# nano_carrier_th.net
KiCad netlist of a schematic drawn in EAGLE
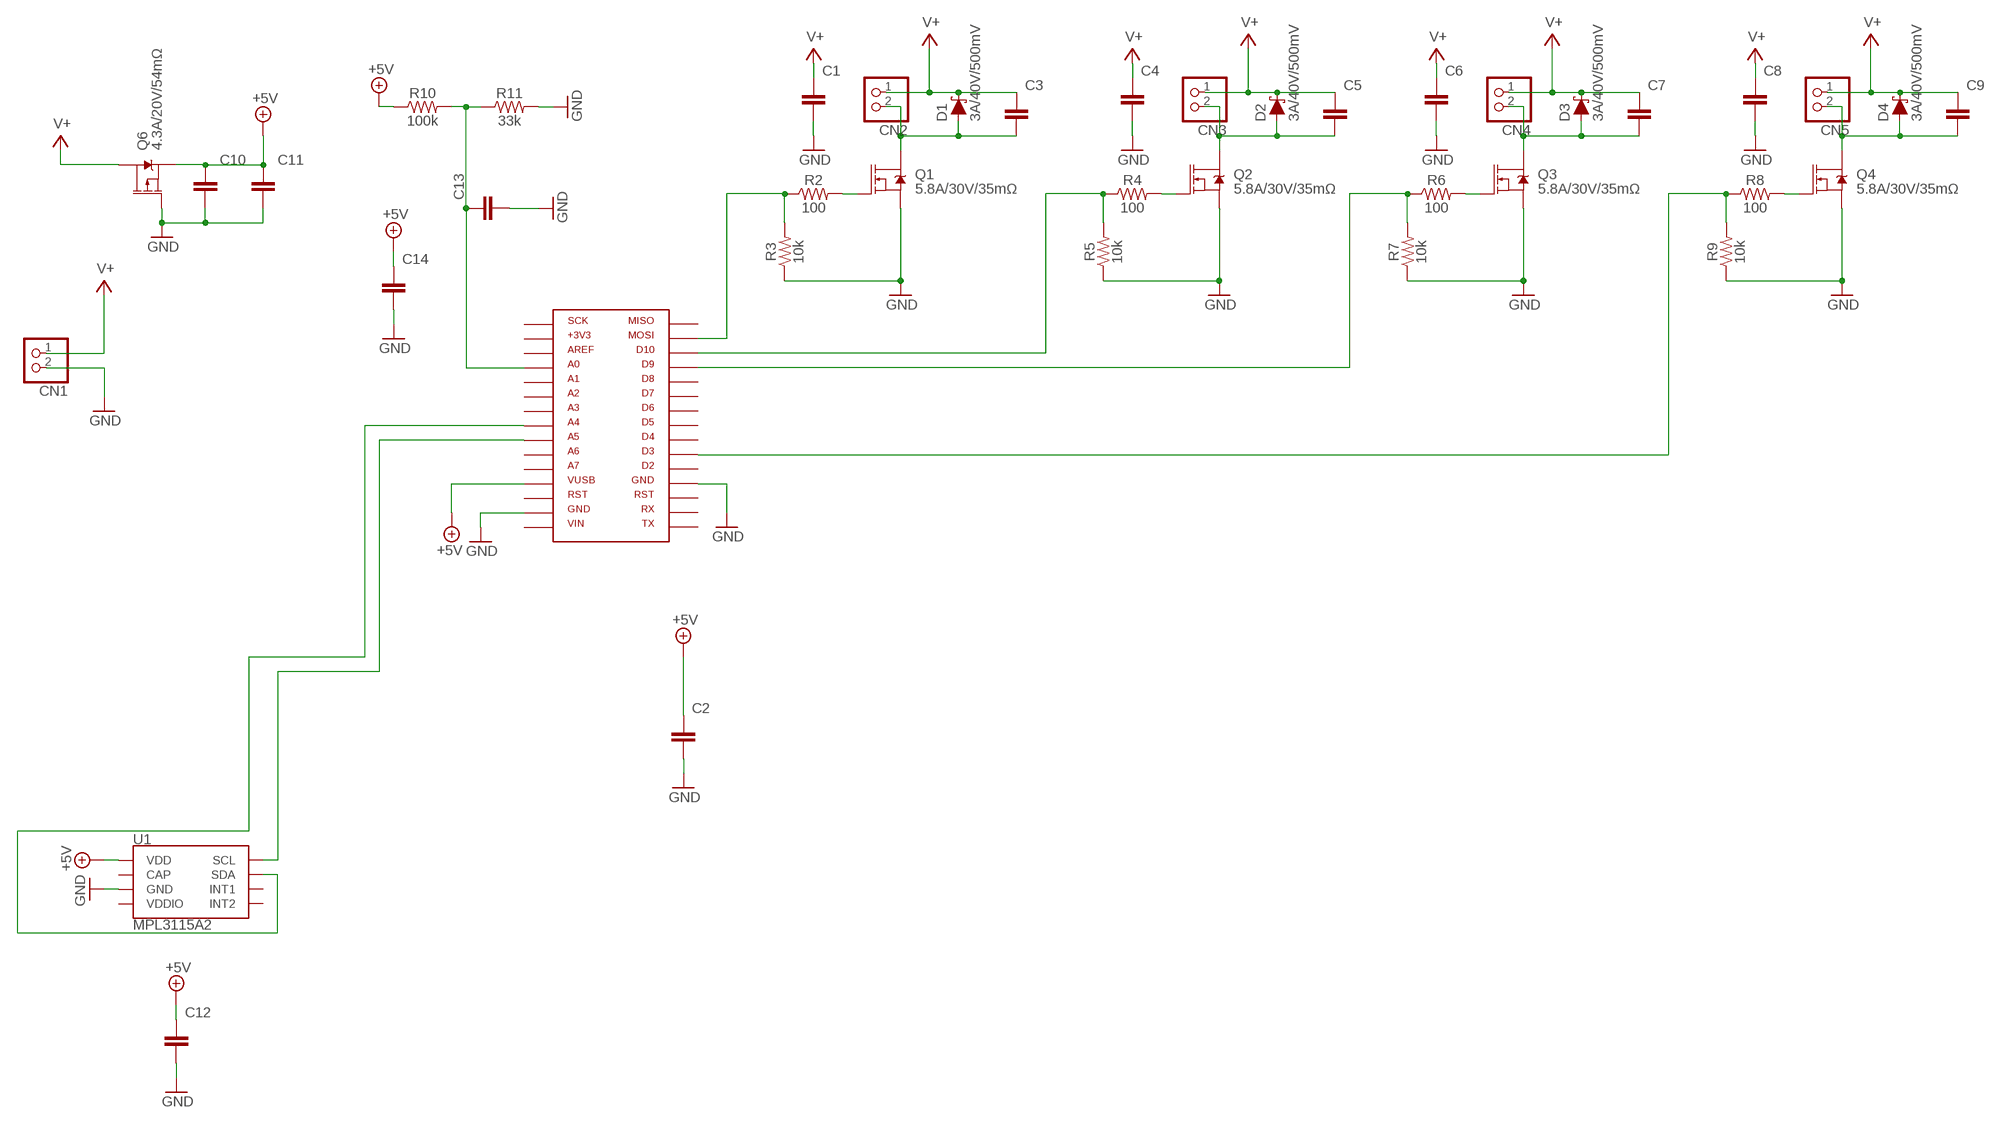
[diagram p0: schematic, sheet 1]

(export (version "E")
  (design (tool "Eeschema 10.0.6"))
  (components
    (comp (ref "C1")
      (value "22uF")
      (footprint "eagle-import:CAPM3216X180")
      (libsource (lib "eagle-import") (part "CTANTALUM-1206(3216-METRIC)_"))
    )
    (comp (ref "C2")
      (value "10uF")
      (footprint "eagle-import:CAPM3216X180")
      (libsource (lib "eagle-import") (part "CTANTALUM-1206(3216-METRIC)_"))
    )
    (comp (ref "C3")
      (value "10nF")
      (footprint "eagle-import:CAPM3216X180")
      (libsource (lib "eagle-import") (part "CTANTALUM-1206(3216-METRIC)_"))
    )
    (comp (ref "C4")
      (value "22uF")
      (footprint "eagle-import:CAPM3216X180")
      (libsource (lib "eagle-import") (part "CTANTALUM-1206(3216-METRIC)_"))
    )
    (comp (ref "C5")
      (value "10nF")
      (footprint "eagle-import:CAPM3216X180")
      (libsource (lib "eagle-import") (part "CTANTALUM-1206(3216-METRIC)_"))
    )
    (comp (ref "C6")
      (value "22uF")
      (footprint "eagle-import:CAPM3216X180")
      (libsource (lib "eagle-import") (part "CTANTALUM-1206(3216-METRIC)_"))
    )
    (comp (ref "C7")
      (value "10nF")
      (footprint "eagle-import:CAPM3216X180")
      (libsource (lib "eagle-import") (part "CTANTALUM-1206(3216-METRIC)_"))
    )
    (comp (ref "C8")
      (value "22uF")
      (footprint "eagle-import:CAPM3216X180")
      (libsource (lib "eagle-import") (part "CTANTALUM-1206(3216-METRIC)_"))
    )
    (comp (ref "C9")
      (value "10nF")
      (footprint "eagle-import:CAPM3216X180")
      (libsource (lib "eagle-import") (part "CTANTALUM-1206(3216-METRIC)_"))
    )
    (comp (ref "C10")
      (value "C_TANTALUM-1206(3216-METRIC)")
      (footprint "eagle-import:CAPM3216X180")
      (libsource (lib "eagle-import") (part "CTANTALUM-1206(3216-METRIC)_"))
    )
    (comp (ref "C11")
      (value "C_TANTALUM-1206(3216-METRIC)")
      (footprint "eagle-import:CAPM3216X180")
      (libsource (lib "eagle-import") (part "CTANTALUM-1206(3216-METRIC)_"))
    )
    (comp (ref "C12")
      (value "22uF")
      (footprint "eagle-import:CAPM3216X180")
      (libsource (lib "eagle-import") (part "CTANTALUM-1206(3216-METRIC)_"))
    )
    (comp (ref "C13")
      (value "22uF")
      (footprint "eagle-import:CAPM3216X180")
      (libsource (lib "eagle-import") (part "CTANTALUM-1206(3216-METRIC)_"))
    )
    (comp (ref "C14")
      (value "22uF")
      (footprint "eagle-import:CAPM3216X180")
      (libsource (lib "eagle-import") (part "CTANTALUM-1206(3216-METRIC)_"))
    )
    (comp (ref "CN1")
      (value "JST_2PIN-THM")
      (footprint "eagle-import:JST-PH-2-THM")
      (libsource (lib "eagle-import") (part "JST_2PIN-THM"))
    )
    (comp (ref "CN2")
      (value "JST_2PIN-THM")
      (footprint "eagle-import:JST-PH-2-THM")
      (libsource (lib "eagle-import") (part "JST_2PIN-THM"))
    )
    (comp (ref "CN3")
      (value "JST_2PIN-THM")
      (footprint "eagle-import:JST-PH-2-THM")
      (libsource (lib "eagle-import") (part "JST_2PIN-THM"))
    )
    (comp (ref "CN4")
      (value "JST_2PIN-THM")
      (footprint "eagle-import:JST-PH-2-THM")
      (libsource (lib "eagle-import") (part "JST_2PIN-THM"))
    )
    (comp (ref "CN5")
      (value "JST_2PIN-THM")
      (footprint "eagle-import:JST-PH-2-THM")
      (libsource (lib "eagle-import") (part "JST_2PIN-THM"))
    )
    (comp (ref "D1")
      (value "3A/40V/500mV")
      (footprint "eagle-import:SMA-DIODE")
      (libsource (lib "eagle-import") (part "DIODE-SCHOTTKY-B340A"))
    )
    (comp (ref "D2")
      (value "3A/40V/500mV")
      (footprint "eagle-import:SMA-DIODE")
      (libsource (lib "eagle-import") (part "DIODE-SCHOTTKY-B340A"))
    )
    (comp (ref "D3")
      (value "3A/40V/500mV")
      (footprint "eagle-import:SMA-DIODE")
      (libsource (lib "eagle-import") (part "DIODE-SCHOTTKY-B340A"))
    )
    (comp (ref "D4")
      (value "3A/40V/500mV")
      (footprint "eagle-import:SMA-DIODE")
      (libsource (lib "eagle-import") (part "DIODE-SCHOTTKY-B340A"))
    )
    (comp (ref "Q1")
      (value "5.8A/30V/35mΩ")
      (footprint "eagle-import:SOT23-3")
      (libsource (lib "eagle-import") (part "MOSFET-NCH-AO3404A"))
    )
    (comp (ref "Q2")
      (value "5.8A/30V/35mΩ")
      (footprint "eagle-import:SOT23-3")
      (libsource (lib "eagle-import") (part "MOSFET-NCH-AO3404A"))
    )
    (comp (ref "Q3")
      (value "5.8A/30V/35mΩ")
      (footprint "eagle-import:SOT23-3")
      (libsource (lib "eagle-import") (part "MOSFET-NCH-AO3404A"))
    )
    (comp (ref "Q4")
      (value "5.8A/30V/35mΩ")
      (footprint "eagle-import:SOT23-3")
      (libsource (lib "eagle-import") (part "MOSFET-NCH-AO3404A"))
    )
    (comp (ref "Q6")
      (value "4.3A/20V/54mΩ")
      (footprint "eagle-import:SOT23-3")
      (libsource (lib "eagle-import") (part "MOSFET_PCH-IRLML2244"))
    )
    (comp (ref "R2")
      (value "100")
      (footprint "eagle-import:0603")
      (libsource (lib "eagle-import") (part "100OHM-0603-1/4W-5%"))
    )
    (comp (ref "R3")
      (value "10k")
      (footprint "eagle-import:0603")
      (libsource (lib "eagle-import") (part "10KOHM-0603-1/10W-1%"))
    )
    (comp (ref "R4")
      (value "100")
      (footprint "eagle-import:0603")
      (libsource (lib "eagle-import") (part "100OHM-0603-1/4W-5%"))
    )
    (comp (ref "R5")
      (value "10k")
      (footprint "eagle-import:0603")
      (libsource (lib "eagle-import") (part "10KOHM-0603-1/10W-1%"))
    )
    (comp (ref "R6")
      (value "100")
      (footprint "eagle-import:0603")
      (libsource (lib "eagle-import") (part "100OHM-0603-1/4W-5%"))
    )
    (comp (ref "R7")
      (value "10k")
      (footprint "eagle-import:0603")
      (libsource (lib "eagle-import") (part "10KOHM-0603-1/10W-1%"))
    )
    (comp (ref "R8")
      (value "100")
      (footprint "eagle-import:0603")
      (libsource (lib "eagle-import") (part "100OHM-0603-1/4W-5%"))
    )
    (comp (ref "R9")
      (value "10k")
      (footprint "eagle-import:0603")
      (libsource (lib "eagle-import") (part "10KOHM-0603-1/10W-1%"))
    )
    (comp (ref "R10")
      (value "100k")
      (footprint "eagle-import:0603")
      (libsource (lib "eagle-import") (part "100KOHM-0603-1/10W-1%"))
    )
    (comp (ref "R11")
      (value "33k")
      (footprint "eagle-import:0603")
      (libsource (lib "eagle-import") (part "33KOHM-0603-1/10W-1%"))
    )
    (comp (ref "U$1")
      (value "NANO-TH")
      (footprint "eagle-import:NANO-TH")
      (libsource (lib "eagle-import") (part "NANO-TH"))
    )
    (comp (ref "U1")
      (value "MPL3115A2")
      (footprint "eagle-import:LGA-8-5X3")
      (libsource (lib "eagle-import") (part "MPL3115A2"))
    )
  )
  (nets
    (net (code "1") (name "+5V") (class "Default")
      (node (ref "C10") (pin "1") (pinfunction "1_1") (pintype "passive"))
      (node (ref "C11") (pin "1") (pinfunction "1_1") (pintype "passive"))
      (node (ref "C12") (pin "1") (pinfunction "1_1") (pintype "passive"))
      (node (ref "C14") (pin "1") (pinfunction "1_1") (pintype "passive"))
      (node (ref "C2") (pin "1") (pinfunction "1_1") (pintype "passive"))
      (node (ref "Q6") (pin "2") (pinfunction "S_2") (pintype "bidirectional"))
      (node (ref "R10") (pin "1") (pinfunction "1_1") (pintype "passive"))
      (node (ref "U$1") (pin "P$12") (pinfunction "P$12_P$12") (pintype "bidirectional"))
      (node (ref "U1") (pin "1") (pinfunction "VDD_1") (pintype "power_in"))
    )
    (net (code "2") (name "/CAP") (class "Default")
      (node (ref "U1") (pin "2") (pinfunction "CAP_2") (pintype "power_in"))
    )
    (net (code "3") (name "/VDDIO") (class "Default")
      (node (ref "U1") (pin "4") (pinfunction "VDDIO_4") (pintype "power_in"))
    )
    (net (code "4") (name "GND") (class "Default")
      (node (ref "C1") (pin "2") (pinfunction "2_2") (pintype "passive"))
      (node (ref "C10") (pin "2") (pinfunction "2_2") (pintype "passive"))
      (node (ref "C11") (pin "2") (pinfunction "2_2") (pintype "passive"))
      (node (ref "C12") (pin "2") (pinfunction "2_2") (pintype "passive"))
      (node (ref "C13") (pin "2") (pinfunction "2_2") (pintype "passive"))
      (node (ref "C14") (pin "2") (pinfunction "2_2") (pintype "passive"))
      (node (ref "C2") (pin "2") (pinfunction "2_2") (pintype "passive"))
      (node (ref "C4") (pin "2") (pinfunction "2_2") (pintype "passive"))
      (node (ref "C6") (pin "2") (pinfunction "2_2") (pintype "passive"))
      (node (ref "C8") (pin "2") (pinfunction "2_2") (pintype "passive"))
      (node (ref "CN1") (pin "2") (pinfunction "1_2") (pintype "passive"))
      (node (ref "Q1") (pin "2") (pinfunction "S_2") (pintype "bidirectional"))
      (node (ref "Q2") (pin "2") (pinfunction "S_2") (pintype "bidirectional"))
      (node (ref "Q3") (pin "2") (pinfunction "S_2") (pintype "bidirectional"))
      (node (ref "Q4") (pin "2") (pinfunction "S_2") (pintype "bidirectional"))
      (node (ref "Q6") (pin "1") (pinfunction "G_1") (pintype "bidirectional"))
      (node (ref "R11") (pin "2") (pinfunction "2_2") (pintype "passive"))
      (node (ref "R3") (pin "1") (pinfunction "1_1") (pintype "passive"))
      (node (ref "R5") (pin "1") (pinfunction "1_1") (pintype "passive"))
      (node (ref "R7") (pin "1") (pinfunction "1_1") (pintype "passive"))
      (node (ref "R9") (pin "1") (pinfunction "1_1") (pintype "passive"))
      (node (ref "U$1") (pin "P$14") (pinfunction "P$14_P$14") (pintype "bidirectional"))
      (node (ref "U$1") (pin "P$19") (pinfunction "P$19_P$19") (pintype "bidirectional"))
      (node (ref "U1") (pin "3") (pinfunction "GND_3") (pintype "power_in"))
    )
    (net (code "5") (name "Net-(C13-Pad1)") (class "Default")
      (node (ref "C13") (pin "1") (pinfunction "1_1") (pintype "passive"))
      (node (ref "R10") (pin "2") (pinfunction "2_2") (pintype "passive"))
      (node (ref "R11") (pin "1") (pinfunction "1_1") (pintype "passive"))
      (node (ref "U$1") (pin "P$4") (pinfunction "P$4_P$4") (pintype "bidirectional"))
    )
    (net (code "6") (name "Net-(CN2-1)") (class "Default")
      (node (ref "C3") (pin "2") (pinfunction "2_2") (pintype "passive"))
      (node (ref "CN2") (pin "2") (pinfunction "1_2") (pintype "passive"))
      (node (ref "D1") (pin "A") (pinfunction "A_A") (pintype "passive"))
      (node (ref "Q1") (pin "3") (pinfunction "D_3") (pintype "bidirectional"))
    )
    (net (code "7") (name "Net-(CN3-1)") (class "Default")
      (node (ref "C5") (pin "2") (pinfunction "2_2") (pintype "passive"))
      (node (ref "CN3") (pin "2") (pinfunction "1_2") (pintype "passive"))
      (node (ref "D2") (pin "A") (pinfunction "A_A") (pintype "passive"))
      (node (ref "Q2") (pin "3") (pinfunction "D_3") (pintype "bidirectional"))
    )
    (net (code "8") (name "Net-(CN4-1)") (class "Default")
      (node (ref "C7") (pin "2") (pinfunction "2_2") (pintype "passive"))
      (node (ref "CN4") (pin "2") (pinfunction "1_2") (pintype "passive"))
      (node (ref "D3") (pin "A") (pinfunction "A_A") (pintype "passive"))
      (node (ref "Q3") (pin "3") (pinfunction "D_3") (pintype "bidirectional"))
    )
    (net (code "9") (name "Net-(CN5-1)") (class "Default")
      (node (ref "C9") (pin "2") (pinfunction "2_2") (pintype "passive"))
      (node (ref "CN5") (pin "2") (pinfunction "1_2") (pintype "passive"))
      (node (ref "D4") (pin "A") (pinfunction "A_A") (pintype "passive"))
      (node (ref "Q4") (pin "3") (pinfunction "D_3") (pintype "bidirectional"))
    )
    (net (code "10") (name "Net-(Q1-G)") (class "Default")
      (node (ref "Q1") (pin "1") (pinfunction "G_1") (pintype "bidirectional"))
      (node (ref "R2") (pin "2") (pinfunction "2_2") (pintype "passive"))
    )
    (net (code "11") (name "Net-(Q2-G)") (class "Default")
      (node (ref "Q2") (pin "1") (pinfunction "G_1") (pintype "bidirectional"))
      (node (ref "R4") (pin "2") (pinfunction "2_2") (pintype "passive"))
    )
    (net (code "12") (name "Net-(Q3-G)") (class "Default")
      (node (ref "Q3") (pin "1") (pinfunction "G_1") (pintype "bidirectional"))
      (node (ref "R6") (pin "2") (pinfunction "2_2") (pintype "passive"))
    )
    (net (code "13") (name "Net-(Q4-G)") (class "Default")
      (node (ref "Q4") (pin "1") (pinfunction "G_1") (pintype "bidirectional"))
      (node (ref "R8") (pin "2") (pinfunction "2_2") (pintype "passive"))
    )
    (net (code "14") (name "Net-(R2-Pad1)") (class "Default")
      (node (ref "R2") (pin "1") (pinfunction "1_1") (pintype "passive"))
      (node (ref "R3") (pin "2") (pinfunction "2_2") (pintype "passive"))
      (node (ref "U$1") (pin "P$29") (pinfunction "P$29_P$29") (pintype "bidirectional"))
    )
    (net (code "15") (name "Net-(R4-Pad1)") (class "Default")
      (node (ref "R4") (pin "1") (pinfunction "1_1") (pintype "passive"))
      (node (ref "R5") (pin "2") (pinfunction "2_2") (pintype "passive"))
      (node (ref "U$1") (pin "P$28") (pinfunction "P$28_P$28") (pintype "bidirectional"))
    )
    (net (code "16") (name "Net-(R6-Pad1)") (class "Default")
      (node (ref "R6") (pin "1") (pinfunction "1_1") (pintype "passive"))
      (node (ref "R7") (pin "2") (pinfunction "2_2") (pintype "passive"))
      (node (ref "U$1") (pin "P$27") (pinfunction "P$27_P$27") (pintype "bidirectional"))
    )
    (net (code "17") (name "Net-(R8-Pad1)") (class "Default")
      (node (ref "R8") (pin "1") (pinfunction "1_1") (pintype "passive"))
      (node (ref "R9") (pin "2") (pinfunction "2_2") (pintype "passive"))
      (node (ref "U$1") (pin "P$21") (pinfunction "P$21_P$21") (pintype "bidirectional"))
    )
    (net (code "18") (name "Net-(U1-SCL)") (class "Default")
      (node (ref "U$1") (pin "P$9") (pinfunction "P$9_P$9") (pintype "bidirectional"))
      (node (ref "U1") (pin "8") (pinfunction "SCL_8") (pintype "bidirectional"))
    )
    (net (code "19") (name "Net-(U1-SDA)") (class "Default")
      (node (ref "U$1") (pin "P$8") (pinfunction "P$8_P$8") (pintype "bidirectional"))
      (node (ref "U1") (pin "7") (pinfunction "SDA_7") (pintype "bidirectional"))
    )
    (net (code "20") (name "V+") (class "Default")
      (node (ref "C1") (pin "1") (pinfunction "1_1") (pintype "passive"))
      (node (ref "C3") (pin "1") (pinfunction "1_1") (pintype "passive"))
      (node (ref "C4") (pin "1") (pinfunction "1_1") (pintype "passive"))
      (node (ref "C5") (pin "1") (pinfunction "1_1") (pintype "passive"))
      (node (ref "C6") (pin "1") (pinfunction "1_1") (pintype "passive"))
      (node (ref "C7") (pin "1") (pinfunction "1_1") (pintype "passive"))
      (node (ref "C8") (pin "1") (pinfunction "1_1") (pintype "passive"))
      (node (ref "C9") (pin "1") (pinfunction "1_1") (pintype "passive"))
      (node (ref "CN1") (pin "1") (pinfunction "2_1") (pintype "passive"))
      (node (ref "CN2") (pin "1") (pinfunction "2_1") (pintype "passive"))
      (node (ref "CN3") (pin "1") (pinfunction "2_1") (pintype "passive"))
      (node (ref "CN4") (pin "1") (pinfunction "2_1") (pintype "passive"))
      (node (ref "CN5") (pin "1") (pinfunction "2_1") (pintype "passive"))
      (node (ref "D1") (pin "C") (pinfunction "C_C") (pintype "passive"))
      (node (ref "D2") (pin "C") (pinfunction "C_C") (pintype "passive"))
      (node (ref "D3") (pin "C") (pinfunction "C_C") (pintype "passive"))
      (node (ref "D4") (pin "C") (pinfunction "C_C") (pintype "passive"))
      (node (ref "Q6") (pin "3") (pinfunction "D_3") (pintype "bidirectional"))
    )
    (net (code "21") (name "unconnected-(U$1-PadP$1)") (class "Default")
      (node (ref "U$1") (pin "P$1") (pinfunction "P$1_P$1") (pintype "bidirectional"))
    )
    (net (code "22") (name "unconnected-(U$1-PadP$2)") (class "Default")
      (node (ref "U$1") (pin "P$2") (pinfunction "P$2_P$2") (pintype "bidirectional"))
    )
    (net (code "23") (name "unconnected-(U$1-PadP$3)") (class "Default")
      (node (ref "U$1") (pin "P$3") (pinfunction "P$3_P$3") (pintype "bidirectional"))
    )
    (net (code "24") (name "unconnected-(U$1-PadP$5)") (class "Default")
      (node (ref "U$1") (pin "P$5") (pinfunction "P$5_P$5") (pintype "bidirectional"))
    )
    (net (code "25") (name "unconnected-(U$1-PadP$6)") (class "Default")
      (node (ref "U$1") (pin "P$6") (pinfunction "P$6_P$6") (pintype "bidirectional"))
    )
    (net (code "26") (name "unconnected-(U$1-PadP$7)") (class "Default")
      (node (ref "U$1") (pin "P$7") (pinfunction "P$7_P$7") (pintype "bidirectional"))
    )
    (net (code "27") (name "unconnected-(U$1-PadP$10)") (class "Default")
      (node (ref "U$1") (pin "P$10") (pinfunction "P$10_P$10") (pintype "bidirectional"))
    )
    (net (code "28") (name "unconnected-(U$1-PadP$11)") (class "Default")
      (node (ref "U$1") (pin "P$11") (pinfunction "P$11_P$11") (pintype "bidirectional"))
    )
    (net (code "29") (name "unconnected-(U$1-PadP$13)") (class "Default")
      (node (ref "U$1") (pin "P$13") (pinfunction "P$13_P$13") (pintype "bidirectional"))
    )
    (net (code "30") (name "unconnected-(U$1-PadP$15)") (class "Default")
      (node (ref "U$1") (pin "P$15") (pinfunction "P$15_P$15") (pintype "bidirectional"))
    )
    (net (code "31") (name "unconnected-(U$1-PadP$16)") (class "Default")
      (node (ref "U$1") (pin "P$16") (pinfunction "P$16_P$16") (pintype "bidirectional"))
    )
    (net (code "32") (name "unconnected-(U$1-PadP$17)") (class "Default")
      (node (ref "U$1") (pin "P$17") (pinfunction "P$17_P$17") (pintype "bidirectional"))
    )
    (net (code "33") (name "unconnected-(U$1-PadP$18)") (class "Default")
      (node (ref "U$1") (pin "P$18") (pinfunction "P$18_P$18") (pintype "bidirectional"))
    )
    (net (code "34") (name "unconnected-(U$1-PadP$20)") (class "Default")
      (node (ref "U$1") (pin "P$20") (pinfunction "P$20_P$20") (pintype "bidirectional"))
    )
    (net (code "35") (name "unconnected-(U$1-PadP$22)") (class "Default")
      (node (ref "U$1") (pin "P$22") (pinfunction "P$22_P$22") (pintype "bidirectional"))
    )
    (net (code "36") (name "unconnected-(U$1-PadP$23)") (class "Default")
      (node (ref "U$1") (pin "P$23") (pinfunction "P$23_P$23") (pintype "bidirectional"))
    )
    (net (code "37") (name "unconnected-(U$1-PadP$24)") (class "Default")
      (node (ref "U$1") (pin "P$24") (pinfunction "P$24_P$24") (pintype "bidirectional"))
    )
    (net (code "38") (name "unconnected-(U$1-PadP$25)") (class "Default")
      (node (ref "U$1") (pin "P$25") (pinfunction "P$25_P$25") (pintype "bidirectional"))
    )
    (net (code "39") (name "unconnected-(U$1-PadP$26)") (class "Default")
      (node (ref "U$1") (pin "P$26") (pinfunction "P$26_P$26") (pintype "bidirectional"))
    )
    (net (code "40") (name "unconnected-(U$1-PadP$30)") (class "Default")
      (node (ref "U$1") (pin "P$30") (pinfunction "P$30_P$30") (pintype "bidirectional"))
    )
    (net (code "41") (name "unconnected-(U1-INT1-Pad6)") (class "Default")
      (node (ref "U1") (pin "6") (pinfunction "INT1_6") (pintype "output"))
    )
    (net (code "42") (name "unconnected-(U1-INT2-Pad5)") (class "Default")
      (node (ref "U1") (pin "5") (pinfunction "INT2_5") (pintype "output"))
    )
  )
)
